# power.net
KiCad netlist of a schematic drawn in Altium Designer
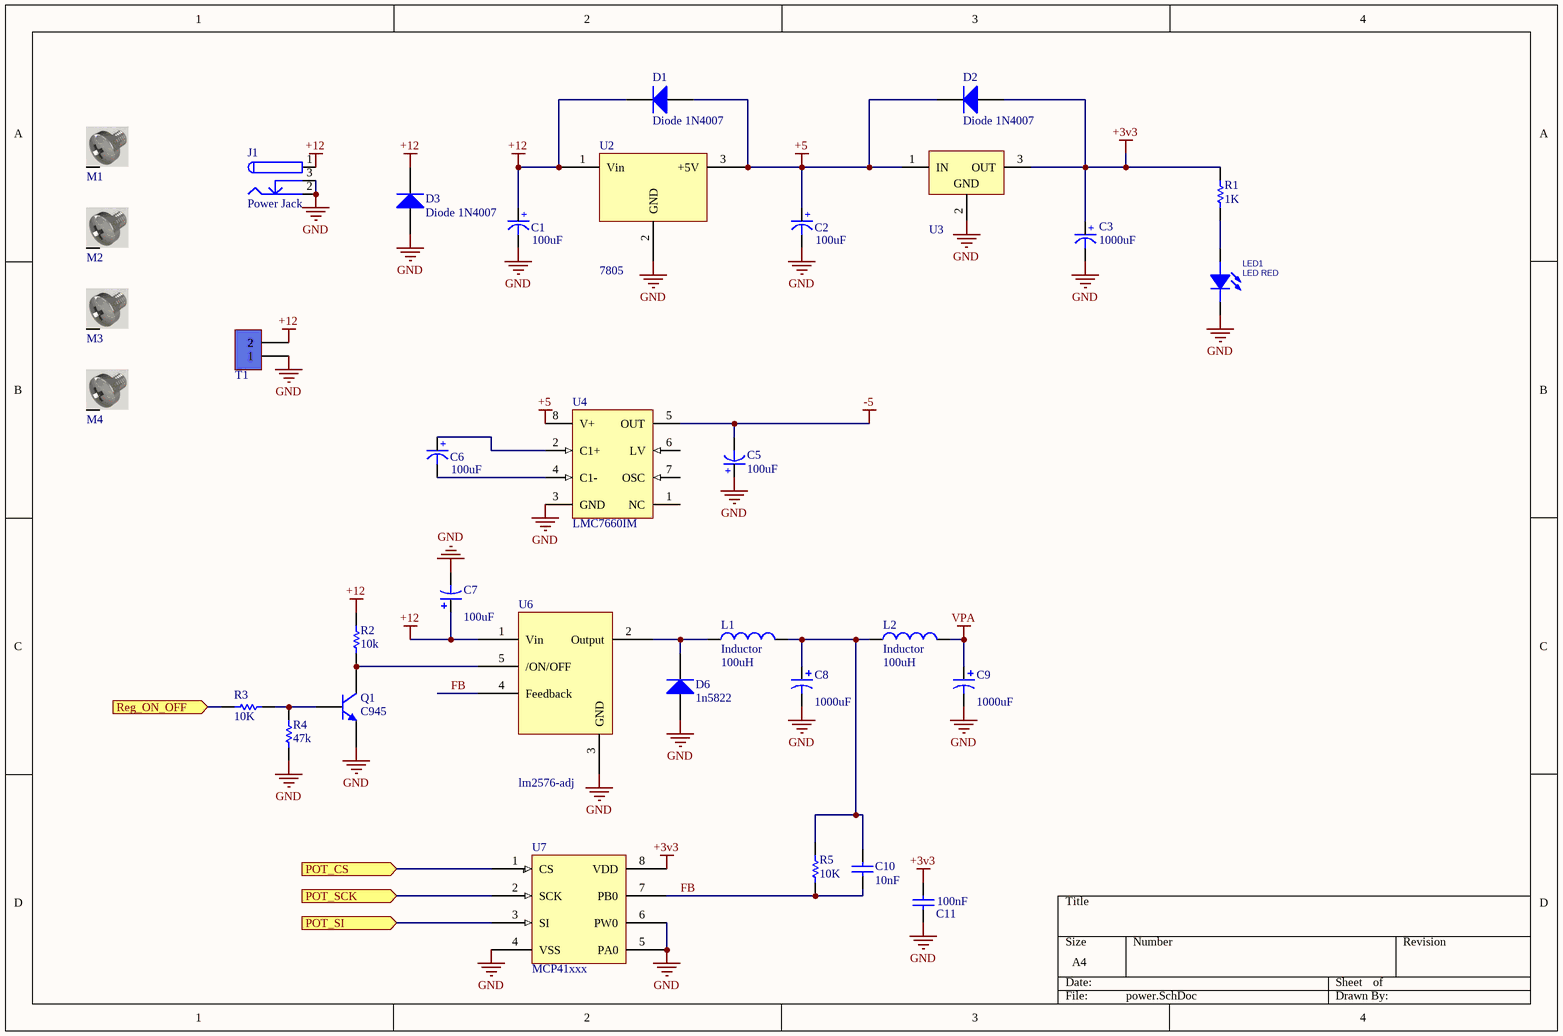
[diagram p0: power.SchDoc]

(export (version "E")
  (design (tool "Eeschema 10.0.6"))
  (components
    (comp (ref "C1")
      (value "100uF")
      (footprint "Cap - 3.5mm - 2")
      (description "Polar Capacitor")
      (fields (field (name "VOLTAGE") "16V") (field (name "DESIGNER") "Saeid Jorablo"))
      (libsource (lib "Altium") (part "Cap-Polar"))
    )
    (comp (ref "C2")
      (value "100uF")
      (footprint "Cap - 3.5mm - 2")
      (description "Polar Capacitor")
      (fields (field (name "VOLTAGE") "16V") (field (name "DESIGNER") "Saeid Jorablo"))
      (libsource (lib "Altium") (part "Cap-Polar"))
    )
    (comp (ref "C3")
      (value "1000uF")
      (footprint "Cap - 3.5mm - 2")
      (description "Polar Capacitor")
      (fields (field (name "VOLTAGE") "16V") (field (name "DESIGNER") "Saeid Jorablo"))
      (libsource (lib "Altium") (part "Cap-Polar"))
    )
    (comp (ref "C5")
      (value "100uF")
      (footprint "Cap - 3.5mm - 2")
      (description "Polar Capacitor")
      (fields (field (name "VOLTAGE") "16V") (field (name "DESIGNER") "Saeid Jorablo"))
      (libsource (lib "Altium") (part "Cap-Polar"))
    )
    (comp (ref "C6")
      (value "100uF")
      (footprint "Cap - 3.5mm - 2")
      (description "Polar Capacitor")
      (fields (field (name "VOLTAGE") "16V") (field (name "DESIGNER") "Saeid Jorablo"))
      (libsource (lib "Altium") (part "Cap-Polar"))
    )
    (comp (ref "C7")
      (value "100uF")
      (footprint "Cap SMD electrolite-6.3mm")
      (description "Polarized Capacitor (Radial)")
      (fields (field (name "PUBLISHER") "Altium Limited"))
      (libsource (lib "Miscellaneous Devices") (part "Cap Pol1"))
    )
    (comp (ref "C8")
      (value "1000uF")
      (footprint "PcbLib1:Cap SMD electrolite-10.3mm")
      (description "Polarized Capacitor (Radial)")
      (fields (field (name "PUBLISHER") "Altium Limited"))
      (libsource (lib "Miscellaneous Devices") (part "Cap Pol1"))
    )
    (comp (ref "C9")
      (value "1000uF")
      (footprint "PcbLib1:Cap SMD electrolite-10.3mm")
      (description "Polarized Capacitor (Radial)")
      (fields (field (name "PUBLISHER") "Altium Limited"))
      (libsource (lib "Miscellaneous Devices") (part "Cap Pol1"))
    )
    (comp (ref "C10")
      (value "10nF")
      (footprint "SMD_CAP_0805")
      (description "CAP-100Nf")
      (fields (field (name "Comment") "Cap"))
      (libsource (lib "Altium library (www.AVRelec.com)") (part "Cap ceramic"))
    )
    (comp (ref "C11")
      (value "100nF")
      (footprint "SMD_CAP_0805")
      (description "CAP-100Nf")
      (fields (field (name "Comment") "Cap"))
      (libsource (lib "Altium library (www.AVRelec.com)") (part "Cap ceramic"))
    )
    (comp (ref "D1")
      (value "Diode 1N4007")
      (footprint "SMA DIODE 2")
      (description "1 Amp General Purpose Rectifier")
      (fields (field (name "PUBLISHER") "Altium Limited"))
      (libsource (lib "Miscellaneous Devices") (part "Diode 1N4007"))
    )
    (comp (ref "D2")
      (value "Diode 1N4007")
      (footprint "SMA DIODE 2")
      (description "1 Amp General Purpose Rectifier")
      (fields (field (name "PUBLISHER") "Altium Limited"))
      (libsource (lib "Miscellaneous Devices") (part "Diode 1N4007"))
    )
    (comp (ref "D3")
      (value "Diode 1N4007")
      (footprint "SMA DIODE 2")
      (description "1 Amp General Purpose Rectifier")
      (fields (field (name "PUBLISHER") "Altium Limited"))
      (libsource (lib "Miscellaneous Devices") (part "Diode 1N4007"))
    )
    (comp (ref "D6")
      (value "1n5822")
      (footprint "DO214AC SMA")
      (description "1 Amp General Purpose Rectifier")
      (fields (field (name "PUBLISHER") "Altium Limited"))
      (libsource (lib "Miscellaneous Devices") (part "Diode 1N4007"))
    )
    (comp (ref "J1")
      (value "Power Jack")
      (footprint "Power Jack")
      (fields (field (name "DESIGNER") "Saeid Jorablo"))
      (libsource (lib "My Library") (part "Power Jack"))
    )
    (comp (ref "L1")
      (value "Inductor")
      (footprint "inductor")
      (fields (field (name "ALTIUM_VALUE") "100uH") (field (name "PUBLISHER") "Altium Limited"))
      (libsource (lib "Miscellaneous Devices") (part "Inductor"))
    )
    (comp (ref "L2")
      (value "Inductor")
      (footprint "inductor")
      (fields (field (name "ALTIUM_VALUE") "100uH") (field (name "PUBLISHER") "Altium Limited"))
      (libsource (lib "Miscellaneous Devices") (part "Inductor"))
    )
    (comp (ref "LED1")
      (value "LED RED")
      (footprint "led_0805")
      (description "Light Emitting Diode")
      (fields (field (name "DESIGNER") "Abbas Basereh"))
      (libsource (lib "Altium (2)") (part "LED 5MM"))
    )
    (comp (ref "M1")
      (value "Screw")
      (footprint "Screw")
      (description "Board Screw With Spacer")
      (libsource (lib "My Library") (part "Board Screw"))
    )
    (comp (ref "M2")
      (value "Screw")
      (footprint "Screw")
      (description "Board Screw With Spacer")
      (libsource (lib "My Library") (part "Board Screw"))
    )
    (comp (ref "M3")
      (value "Screw")
      (footprint "Screw")
      (description "Board Screw With Spacer")
      (libsource (lib "My Library") (part "Board Screw"))
    )
    (comp (ref "M4")
      (value "Screw")
      (footprint "Screw")
      (description "Board Screw With Spacer")
      (libsource (lib "My Library") (part "Board Screw"))
    )
    (comp (ref "Q1")
      (value "C945")
      (footprint "SOT23_N")
      (description "NPN Silicon Epitaxial Planar Transistor")
      (fields (field (name "PUBLISHER") "Abbas Basereh"))
      (libsource (lib "Altium (2)") (part "C945"))
    )
    (comp (ref "R1")
      (value "1K")
      (footprint "RES 0805 (2012X06L)")
      (description "RES Axial 0.25W")
      (fields (field (name "DESIGNER") "Abbas Basereh"))
      (libsource (lib "Altium (2)") (part "RES Axial 0.25W"))
    )
    (comp (ref "R2")
      (value "10k")
      (footprint "RES 0805 (2012X06L)")
      (description "Resistor")
      (fields (field (name "Comment") "Res1") (field (name "PUBLISHER") "Altium Limited"))
      (libsource (lib "Miscellaneous Devices") (part "Res1"))
    )
    (comp (ref "R3")
      (value "10K")
      (footprint "RES 0805 (2012X06L)")
      (description "Resistor")
      (fields (field (name "Comment") "Res1") (field (name "PUBLISHER") "Altium Limited"))
      (libsource (lib "Miscellaneous Devices") (part "Res1"))
    )
    (comp (ref "R4")
      (value "47k")
      (footprint "RES 0805 (2012X06L)")
      (description "Resistor")
      (fields (field (name "Comment") "Res1") (field (name "PUBLISHER") "Altium Limited"))
      (libsource (lib "Miscellaneous Devices") (part "Res1"))
    )
    (comp (ref "R5")
      (value "10K")
      (footprint "RES 0805 (2012X06L)")
      (description "RES Axial 0.25W")
      (fields (field (name "DESIGNER") "Abbas Basereh"))
      (libsource (lib "Altium (2)") (part "RES Axial 0.25W"))
    )
    (comp (ref "T1")
      (value "Terminal")
      (footprint "Terminal 1*2_1")
      (description "Terminal 2 Pin 250VAC 16A")
      (fields (field (name "DESIGNER") "Seyed Mohsen Ghasemain") (field (name "E-MAIL") "picpars@gmail.com"))
      (libsource (lib "PicPars.com_usefully_Library") (part "Terminal 1*2"))
    )
    (comp (ref "U2")
      (value "7805")
      (footprint "REG-7805-WALL")
      (description "Regulator")
      (libsource (lib "Altium library (www.AVRelec.com)") (part "7805"))
    )
    (comp (ref "U3")
      (value "Voltage Regulator")
      (footprint "REG-7805-WALL")
      (description "Voltage Regulator 3.3 Volt")
      (libsource (lib "Altium") (part "LF33"))
    )
    (comp (ref "U4")
      (value "LMC7660IM")
      (footprint "M08A_N")
      (description "Switched Capacitor Voltage Converter")
      (fields
        (field (name "MANUFACTURER") "National Semiconductor")
        (field (name "DIGIKEYPARTNUMBER") "LMC7660IM-ND")
        (field (name "PUBLISHER") "Altium Limited")
      )
      (libsource (lib "NSC Switch Caps") (part "LMC7660IM"))
    )
    (comp (ref "U6") (value "lm2576-adj") (footprint "2596") (libsource (lib "No.2") (part "lm2596")))
    (comp (ref "U7") (value "MCP41xxx") (footprint "SO8_M") (libsource (lib "PA_sch") (part "MCP41xxx")))
  )
  (nets
    (net (code "1") (name "+3v3") (class "Default")
      (node (ref "C11") (pin "2") (pinfunction "2_2") (pintype "passive"))
      (node (ref "C3") (pin "1") (pinfunction "+_1") (pintype "passive"))
      (node (ref "D2") (pin "1") (pinfunction "A_1") (pintype "passive"))
      (node (ref "R1") (pin "2") (pinfunction "2_2") (pintype "passive"))
      (node (ref "U3") (pin "3") (pinfunction "OUT_3") (pintype "passive"))
      (node (ref "U7") (pin "8") (pinfunction "VDD_8") (pintype "power_in"))
    )
    (net (code "2") (name "+5") (class "Default")
      (node (ref "C2") (pin "1") (pinfunction "+_1") (pintype "passive"))
      (node (ref "D1") (pin "1") (pinfunction "A_1") (pintype "passive"))
      (node (ref "D2") (pin "2") (pinfunction "K_2") (pintype "passive"))
      (node (ref "U2") (pin "3") (pinfunction "+5V_3") (pintype "power_in"))
      (node (ref "U3") (pin "1") (pinfunction "IN_1") (pintype "passive"))
      (node (ref "U4") (pin "8") (pinfunction "V+_8") (pintype "power_in"))
    )
    (net (code "3") (name "+12") (class "Default")
      (node (ref "C1") (pin "1") (pinfunction "+_1") (pintype "passive"))
      (node (ref "C7") (pin "1") (pinfunction "1_1") (pintype "passive"))
      (node (ref "D1") (pin "2") (pinfunction "K_2") (pintype "passive"))
      (node (ref "D3") (pin "2") (pinfunction "K_2") (pintype "passive"))
      (node (ref "J1") (pin "1") (pinfunction "1_1") (pintype "power_in"))
      (node (ref "R2") (pin "2") (pinfunction "2_2") (pintype "passive"))
      (node (ref "T1") (pin "2") (pinfunction "2_2") (pintype "passive"))
      (node (ref "U2") (pin "1") (pinfunction "Vin_1") (pintype "power_in"))
      (node (ref "U6") (pin "1") (pinfunction "Vin_1") (pintype "power_in"))
    )
    (net (code "4") (name "-5") (class "Default")
      (node (ref "C5") (pin "2") (pinfunction "-_2") (pintype "passive"))
      (node (ref "U4") (pin "5") (pinfunction "OUT_5") (pintype "power_in"))
    )
    (net (code "5") (name "/FB") (class "Default")
      (node (ref "C10") (pin "2") (pinfunction "2_2") (pintype "passive"))
      (node (ref "R5") (pin "1") (pinfunction "1_1") (pintype "passive"))
      (node (ref "U6") (pin "4") (pinfunction "Feedback_4") (pintype "power_in"))
      (node (ref "U7") (pin "7") (pinfunction "PB0_7") (pintype "passive"))
    )
    (net (code "6") (name "/POT_CS") (class "Default")
      (node (ref "U7") (pin "1") (pinfunction "CS_1") (pintype "input"))
    )
    (net (code "7") (name "/POT_SCK") (class "Default")
      (node (ref "U7") (pin "2") (pinfunction "SCK_2") (pintype "input"))
    )
    (net (code "8") (name "/POT_SI") (class "Default")
      (node (ref "U7") (pin "3") (pinfunction "SI_3") (pintype "input"))
    )
    (net (code "9") (name "/Reg_ON_OFF") (class "Default")
      (node (ref "R3") (pin "1") (pinfunction "1_1") (pintype "passive"))
    )
    (net (code "10") (name "GND") (class "Default")
      (node (ref "C1") (pin "2") (pinfunction "-_2") (pintype "passive"))
      (node (ref "C11") (pin "1") (pinfunction "1_1") (pintype "passive"))
      (node (ref "C2") (pin "2") (pinfunction "-_2") (pintype "passive"))
      (node (ref "C3") (pin "2") (pinfunction "-_2") (pintype "passive"))
      (node (ref "C5") (pin "1") (pinfunction "+_1") (pintype "passive"))
      (node (ref "C7") (pin "2") (pinfunction "2_2") (pintype "passive"))
      (node (ref "C8") (pin "2") (pinfunction "2_2") (pintype "passive"))
      (node (ref "C9") (pin "2") (pinfunction "2_2") (pintype "passive"))
      (node (ref "D3") (pin "1") (pinfunction "A_1") (pintype "passive"))
      (node (ref "D6") (pin "1") (pinfunction "A_1") (pintype "passive"))
      (node (ref "J1") (pin "2") (pinfunction "2_2") (pintype "power_in"))
      (node (ref "J1") (pin "3") (pinfunction "3_3") (pintype "power_in"))
      (node (ref "LED1") (pin "2") (pinfunction "CATHODE_2") (pintype "passive"))
      (node (ref "Q1") (pin "2") (pinfunction "E_2") (pintype "passive"))
      (node (ref "R4") (pin "1") (pinfunction "1_1") (pintype "passive"))
      (node (ref "T1") (pin "1") (pinfunction "1_1") (pintype "passive"))
      (node (ref "U2") (pin "2") (pinfunction "GND_2") (pintype "power_in"))
      (node (ref "U3") (pin "2") (pinfunction "GND_2") (pintype "passive"))
      (node (ref "U4") (pin "3") (pinfunction "GND_3") (pintype "power_in"))
      (node (ref "U6") (pin "3") (pinfunction "GND_3") (pintype "power_in"))
      (node (ref "U7") (pin "4") (pinfunction "VSS_4") (pintype "power_in"))
      (node (ref "U7") (pin "5") (pinfunction "PA0_5") (pintype "passive"))
      (node (ref "U7") (pin "6") (pinfunction "PW0_6") (pintype "passive"))
    )
    (net (code "11") (name "Net-(C6-+)") (class "Default")
      (node (ref "C6") (pin "1") (pinfunction "+_1") (pintype "passive"))
      (node (ref "U4") (pin "2") (pinfunction "C1+_2") (pintype "input"))
    )
    (net (code "12") (name "Net-(C6--)") (class "Default")
      (node (ref "C6") (pin "2") (pinfunction "-_2") (pintype "passive"))
      (node (ref "U4") (pin "4") (pinfunction "C1-_4") (pintype "input"))
    )
    (net (code "13") (name "Net-(C10-Pad1)") (class "Default")
      (node (ref "C10") (pin "1") (pinfunction "1_1") (pintype "passive"))
      (node (ref "C8") (pin "1") (pinfunction "1_1") (pintype "passive"))
      (node (ref "L1") (pin "2") (pinfunction "2_2") (pintype "passive"))
      (node (ref "L2") (pin "1") (pinfunction "1_1") (pintype "passive"))
      (node (ref "R5") (pin "2") (pinfunction "2_2") (pintype "passive"))
    )
    (net (code "14") (name "Net-(D6-K)") (class "Default")
      (node (ref "D6") (pin "2") (pinfunction "K_2") (pintype "passive"))
      (node (ref "L1") (pin "1") (pinfunction "1_1") (pintype "passive"))
      (node (ref "U6") (pin "2") (pinfunction "Output_2") (pintype "power_in"))
    )
    (net (code "15") (name "Net-(LED1-ANODE)") (class "Default")
      (node (ref "LED1") (pin "1") (pinfunction "ANODE_1") (pintype "passive"))
      (node (ref "R1") (pin "1") (pinfunction "1_1") (pintype "passive"))
    )
    (net (code "16") (name "Net-(Q1-B)") (class "Default")
      (node (ref "Q1") (pin "1") (pinfunction "B_1") (pintype "passive"))
      (node (ref "R3") (pin "2") (pinfunction "2_2") (pintype "passive"))
      (node (ref "R4") (pin "2") (pinfunction "2_2") (pintype "passive"))
    )
    (net (code "17") (name "Net-(Q1-C)") (class "Default")
      (node (ref "Q1") (pin "3") (pinfunction "C_3") (pintype "passive"))
      (node (ref "R2") (pin "1") (pinfunction "1_1") (pintype "passive"))
      (node (ref "U6") (pin "5") (pinfunction "/ON/OFF_5") (pintype "power_in"))
    )
    (net (code "18") (name "VPA") (class "Default")
      (node (ref "C9") (pin "1") (pinfunction "1_1") (pintype "passive"))
      (node (ref "L2") (pin "2") (pinfunction "2_2") (pintype "passive"))
    )
    (net (code "19") (name "unconnected-(M1-PadS)") (class "Default")
      (node (ref "M1") (pin "S") (pinfunction "S_S") (pintype "passive"))
    )
    (net (code "20") (name "unconnected-(M2-PadS)") (class "Default")
      (node (ref "M2") (pin "S") (pinfunction "S_S") (pintype "passive"))
    )
    (net (code "21") (name "unconnected-(M3-PadS)") (class "Default")
      (node (ref "M3") (pin "S") (pinfunction "S_S") (pintype "passive"))
    )
    (net (code "22") (name "unconnected-(M4-PadS)") (class "Default")
      (node (ref "M4") (pin "S") (pinfunction "S_S") (pintype "passive"))
    )
    (net (code "23") (name "unconnected-(U4-LV-Pad6)") (class "Default")
      (node (ref "U4") (pin "6") (pinfunction "LV_6") (pintype "input"))
    )
    (net (code "24") (name "unconnected-(U4-NC-Pad1)") (class "Default")
      (node (ref "U4") (pin "1") (pinfunction "NC_1") (pintype "passive"))
    )
    (net (code "25") (name "unconnected-(U4-OSC-Pad7)") (class "Default")
      (node (ref "U4") (pin "7") (pinfunction "OSC_7") (pintype "input"))
    )
  )
)
